# BT_Controller.net
KiCad netlist of a schematic drawn in EAGLE
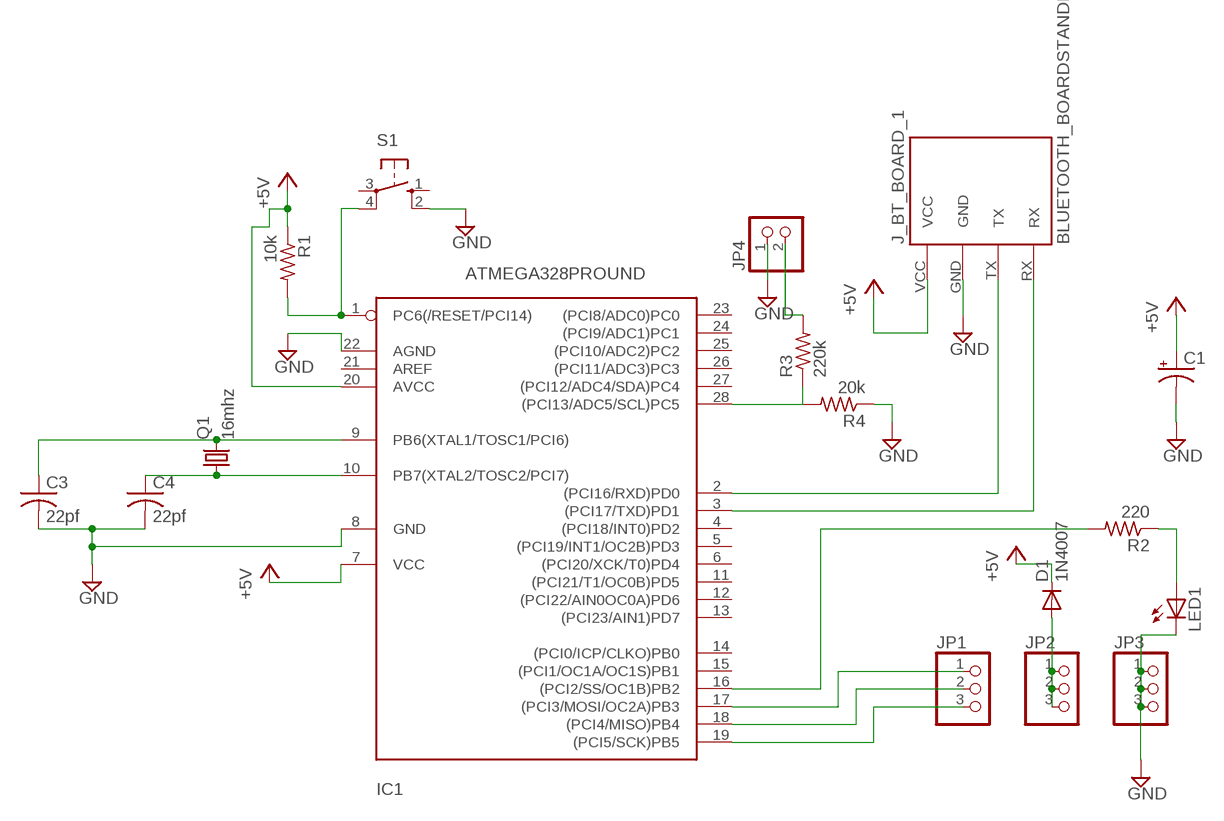
[diagram p0: schematic, sheet 1]

(export (version "E")
  (design (tool "Eeschema 10.0.6"))
  (components
    (comp (ref "C1")
      (value "CPOL-USE2,5-6E")
      (footprint "eagle-import:E2,5-6E")
      (libsource (lib "eagle-import") (part "CPOL-USE2,5-6E"))
    )
    (comp (ref "C3")
      (value "22pf")
      (footprint "eagle-import:C050-024X044")
      (libsource (lib "eagle-import") (part "C-US050-024X044"))
    )
    (comp (ref "C4")
      (value "22pf")
      (footprint "eagle-import:C050-024X044")
      (libsource (lib "eagle-import") (part "C-US050-024X044"))
    )
    (comp (ref "D1")
      (value "1N4007")
      (footprint "eagle-import:DO41-10")
      (libsource (lib "eagle-import") (part "1N4004"))
    )
    (comp (ref "IC1")
      (value "ATMEGA328PROUND")
      (footprint "eagle-import:DIL28-3-ROUND")
      (libsource (lib "eagle-import") (part "ATMEGA328PROUND"))
    )
    (comp (ref "JP1")
      (value "PINHD-1X3")
      (footprint "eagle-import:1X03")
      (libsource (lib "eagle-import") (part "PINHD-1X3"))
    )
    (comp (ref "JP2")
      (value "PINHD-1X3")
      (footprint "eagle-import:1X03")
      (libsource (lib "eagle-import") (part "PINHD-1X3"))
    )
    (comp (ref "JP3")
      (value "PINHD-1X3")
      (footprint "eagle-import:1X03")
      (libsource (lib "eagle-import") (part "PINHD-1X3"))
    )
    (comp (ref "JP4")
      (value "PINHD-1X2")
      (footprint "eagle-import:1X02")
      (libsource (lib "eagle-import") (part "PINHD-1X2"))
    )
    (comp (ref "J_BT_BOARD_1")
      (value "BLUETOOTH_BOARDSTANDING")
      (footprint "eagle-import:BT_BOARD_FOOTPRINT_STANDING")
      (libsource (lib "eagle-import") (part "BLUETOOTH_BOARDSTANDING"))
    )
    (comp (ref "LED1")
      (value "LED5MM")
      (footprint "eagle-import:LED5MM")
      (libsource (lib "eagle-import") (part "LED5MM"))
    )
    (comp (ref "Q1")
      (value "16mhz")
      (footprint "eagle-import:HC49U70")
      (libsource (lib "eagle-import") (part "CRYSTALHC49U70"))
    )
    (comp (ref "R1")
      (value "10k")
      (footprint "eagle-import:0207_7")
      (libsource (lib "eagle-import") (part "R-US_0207/7"))
    )
    (comp (ref "R2")
      (value "220")
      (footprint "eagle-import:0207_7")
      (libsource (lib "eagle-import") (part "R-US_0207/7"))
    )
    (comp (ref "R3")
      (value "220k")
      (footprint "eagle-import:0207_7")
      (libsource (lib "eagle-import") (part "R-US_0207/7"))
    )
    (comp (ref "R4")
      (value "20k")
      (footprint "eagle-import:0207_7")
      (libsource (lib "eagle-import") (part "R-US_0207/7"))
    )
    (comp (ref "S1")
      (value "10-XX")
      (footprint "eagle-import:B3F-10XX")
      (fields (field (name "MPN") "B3F-1000"))
      (libsource (lib "eagle-import") (part "10-XX"))
    )
  )
  (nets
    (net (code "1") (name "+5V") (class "Default")
      (node (ref "C1") (pin "+") (pinfunction "+_+") (pintype "passive"))
      (node (ref "D1") (pin "C") (pinfunction "C_C") (pintype "passive"))
      (node (ref "IC1") (pin "20") (pinfunction "AVCC_20") (pintype "bidirectional"))
      (node (ref "IC1") (pin "7") (pinfunction "VCC_7") (pintype "bidirectional"))
      (node (ref "J_BT_BOARD_1") (pin "VCC") (pinfunction "VCC_VCC") (pintype "bidirectional"))
      (node (ref "R1") (pin "1") (pinfunction "1_1") (pintype "passive"))
    )
    (net (code "2") (name "GND") (class "Default")
      (node (ref "C1") (pin "-") (pinfunction "-_-") (pintype "passive"))
      (node (ref "C3") (pin "2") (pinfunction "2_2") (pintype "passive"))
      (node (ref "C4") (pin "2") (pinfunction "2_2") (pintype "passive"))
      (node (ref "IC1") (pin "22") (pinfunction "AGND_22") (pintype "bidirectional"))
      (node (ref "IC1") (pin "8") (pinfunction "GND_8") (pintype "bidirectional"))
      (node (ref "JP3") (pin "1") (pinfunction "1_1") (pintype "passive"))
      (node (ref "JP3") (pin "2") (pinfunction "2_2") (pintype "passive"))
      (node (ref "JP3") (pin "3") (pinfunction "3_3") (pintype "passive"))
      (node (ref "JP4") (pin "1") (pinfunction "1_1") (pintype "passive"))
      (node (ref "J_BT_BOARD_1") (pin "GND") (pinfunction "GND_GND") (pintype "bidirectional"))
      (node (ref "LED1") (pin "K") (pinfunction "C_K") (pintype "passive"))
      (node (ref "R4") (pin "1") (pinfunction "1_1") (pintype "passive"))
      (node (ref "S1") (pin "2") (pinfunction "S1_2") (pintype "passive"))
    )
    (net (code "3") (name "Net-(D1-PadA)") (class "Default")
      (node (ref "D1") (pin "A") (pinfunction "A_A") (pintype "passive"))
      (node (ref "JP2") (pin "1") (pinfunction "1_1") (pintype "passive"))
      (node (ref "JP2") (pin "2") (pinfunction "2_2") (pintype "passive"))
      (node (ref "JP2") (pin "3") (pinfunction "3_3") (pintype "passive"))
    )
    (net (code "4") (name "Net-(IC1-(PCI2{slash}SS{slash}OC1B)PB2)") (class "Default")
      (node (ref "IC1") (pin "16") (pinfunction "(PCI2/SS/OC1B)PB2_16") (pintype "bidirectional"))
      (node (ref "R2") (pin "2") (pinfunction "2_2") (pintype "passive"))
    )
    (net (code "5") (name "Net-(IC1-(PCI3{slash}MOSI{slash}OC2A)PB3)") (class "Default")
      (node (ref "IC1") (pin "17") (pinfunction "(PCI3/MOSI/OC2A)PB3_17") (pintype "bidirectional"))
      (node (ref "JP1") (pin "1") (pinfunction "1_1") (pintype "passive"))
    )
    (net (code "6") (name "Net-(IC1-(PCI4{slash}MISO)PB4)") (class "Default")
      (node (ref "IC1") (pin "18") (pinfunction "(PCI4/MISO)PB4_18") (pintype "bidirectional"))
      (node (ref "JP1") (pin "2") (pinfunction "2_2") (pintype "passive"))
    )
    (net (code "7") (name "Net-(IC1-(PCI5{slash}SCK)PB5)") (class "Default")
      (node (ref "IC1") (pin "19") (pinfunction "(PCI5/SCK)PB5_19") (pintype "bidirectional"))
      (node (ref "JP1") (pin "3") (pinfunction "3_3") (pintype "passive"))
    )
    (net (code "8") (name "Net-(IC1-(PCI13{slash}ADC5{slash}SCL)PC5)") (class "Default")
      (node (ref "IC1") (pin "28") (pinfunction "(PCI13/ADC5/SCL)PC5_28") (pintype "bidirectional"))
      (node (ref "R3") (pin "1") (pinfunction "1_1") (pintype "passive"))
      (node (ref "R4") (pin "2") (pinfunction "2_2") (pintype "passive"))
    )
    (net (code "9") (name "Net-(IC1-(PCI16{slash}RXD)PD0)") (class "Default")
      (node (ref "IC1") (pin "2") (pinfunction "(PCI16/RXD)PD0_2") (pintype "bidirectional"))
      (node (ref "J_BT_BOARD_1") (pin "TX") (pinfunction "TX_TX") (pintype "bidirectional"))
    )
    (net (code "10") (name "Net-(IC1-(PCI17{slash}TXD)PD1)") (class "Default")
      (node (ref "IC1") (pin "3") (pinfunction "(PCI17/TXD)PD1_3") (pintype "bidirectional"))
      (node (ref "J_BT_BOARD_1") (pin "RX") (pinfunction "RX_RX") (pintype "bidirectional"))
    )
    (net (code "11") (name "Net-(IC1-PB6(XTAL1{slash}TOSC1{slash}PCI6))") (class "Default")
      (node (ref "C3") (pin "1") (pinfunction "1_1") (pintype "passive"))
      (node (ref "IC1") (pin "9") (pinfunction "PB6(XTAL1/TOSC1/PCI6)_9") (pintype "bidirectional"))
      (node (ref "Q1") (pin "2") (pinfunction "2_2") (pintype "passive"))
    )
    (net (code "12") (name "Net-(IC1-PB7(XTAL2{slash}TOSC2{slash}PCI7))") (class "Default")
      (node (ref "C4") (pin "1") (pinfunction "1_1") (pintype "passive"))
      (node (ref "IC1") (pin "10") (pinfunction "PB7(XTAL2/TOSC2/PCI7)_10") (pintype "bidirectional"))
      (node (ref "Q1") (pin "1") (pinfunction "1_1") (pintype "passive"))
    )
    (net (code "13") (name "Net-(IC1-PC6({slash}RESET{slash}PCI14))") (class "Default")
      (node (ref "IC1") (pin "1") (pinfunction "PC6(/RESET/PCI14)_1") (pintype "bidirectional"))
      (node (ref "R1") (pin "2") (pinfunction "2_2") (pintype "passive"))
      (node (ref "S1") (pin "4") (pinfunction "P1_4") (pintype "passive"))
    )
    (net (code "14") (name "Net-(JP4-Pad2)") (class "Default")
      (node (ref "JP4") (pin "2") (pinfunction "2_2") (pintype "passive"))
      (node (ref "R3") (pin "2") (pinfunction "2_2") (pintype "passive"))
    )
    (net (code "15") (name "Net-(LED1-PadA)") (class "Default")
      (node (ref "LED1") (pin "A") (pinfunction "A_A") (pintype "passive"))
      (node (ref "R2") (pin "1") (pinfunction "1_1") (pintype "passive"))
    )
    (net (code "16") (name "unconnected-(IC1-(PCI0{slash}ICP{slash}CLKO)PB0-Pad14)") (class "Default")
      (node (ref "IC1") (pin "14") (pinfunction "(PCI0/ICP/CLKO)PB0_14") (pintype "bidirectional"))
    )
    (net (code "17") (name "unconnected-(IC1-(PCI1{slash}OC1A{slash}OC1S)PB1-Pad15)") (class "Default")
      (node (ref "IC1") (pin "15") (pinfunction "(PCI1/OC1A/OC1S)PB1_15") (pintype "bidirectional"))
    )
    (net (code "18") (name "unconnected-(IC1-(PCI8{slash}ADC0)PC0-Pad23)") (class "Default")
      (node (ref "IC1") (pin "23") (pinfunction "(PCI8/ADC0)PC0_23") (pintype "bidirectional"))
    )
    (net (code "19") (name "unconnected-(IC1-(PCI9{slash}ADC1)PC1-Pad24)") (class "Default")
      (node (ref "IC1") (pin "24") (pinfunction "(PCI9/ADC1)PC1_24") (pintype "bidirectional"))
    )
    (net (code "20") (name "unconnected-(IC1-(PCI10{slash}ADC2)PC2-Pad25)") (class "Default")
      (node (ref "IC1") (pin "25") (pinfunction "(PCI10/ADC2)PC2_25") (pintype "bidirectional"))
    )
    (net (code "21") (name "unconnected-(IC1-(PCI11{slash}ADC3)PC3-Pad26)") (class "Default")
      (node (ref "IC1") (pin "26") (pinfunction "(PCI11/ADC3)PC3_26") (pintype "bidirectional"))
    )
    (net (code "22") (name "unconnected-(IC1-(PCI12{slash}ADC4{slash}SDA)PC4-Pad27)") (class "Default")
      (node (ref "IC1") (pin "27") (pinfunction "(PCI12/ADC4/SDA)PC4_27") (pintype "bidirectional"))
    )
    (net (code "23") (name "unconnected-(IC1-(PCI18{slash}INT0)PD2-Pad4)") (class "Default")
      (node (ref "IC1") (pin "4") (pinfunction "(PCI18/INT0)PD2_4") (pintype "bidirectional"))
    )
    (net (code "24") (name "unconnected-(IC1-(PCI19{slash}INT1{slash}OC2B)PD3-Pad5)") (class "Default")
      (node (ref "IC1") (pin "5") (pinfunction "(PCI19/INT1/OC2B)PD3_5") (pintype "bidirectional"))
    )
    (net (code "25") (name "unconnected-(IC1-(PCI20{slash}XCK{slash}T0)PD4-Pad6)") (class "Default")
      (node (ref "IC1") (pin "6") (pinfunction "(PCI20/XCK/T0)PD4_6") (pintype "bidirectional"))
    )
    (net (code "26") (name "unconnected-(IC1-(PCI21{slash}T1{slash}OC0B)PD5-Pad11)") (class "Default")
      (node (ref "IC1") (pin "11") (pinfunction "(PCI21/T1/OC0B)PD5_11") (pintype "bidirectional"))
    )
    (net (code "27") (name "unconnected-(IC1-(PCI22{slash}AIN0OC0A)PD6-Pad12)") (class "Default")
      (node (ref "IC1") (pin "12") (pinfunction "(PCI22/AIN0OC0A)PD6_12") (pintype "bidirectional"))
    )
    (net (code "28") (name "unconnected-(IC1-(PCI23{slash}AIN1)PD7-Pad13)") (class "Default")
      (node (ref "IC1") (pin "13") (pinfunction "(PCI23/AIN1)PD7_13") (pintype "bidirectional"))
    )
    (net (code "29") (name "unconnected-(IC1-AREF-Pad21)") (class "Default")
      (node (ref "IC1") (pin "21") (pinfunction "AREF_21") (pintype "bidirectional"))
    )
    (net (code "30") (name "unconnected-(S1-P-Pad3)") (class "Default")
      (node (ref "S1") (pin "3") (pinfunction "P_3") (pintype "passive"))
    )
    (net (code "31") (name "unconnected-(S1-S-Pad1)") (class "Default")
      (node (ref "S1") (pin "1") (pinfunction "S_1") (pintype "passive"))
    )
  )
)
